# Power_Supply.net
KiCad netlist of a schematic drawn in Altium Designer
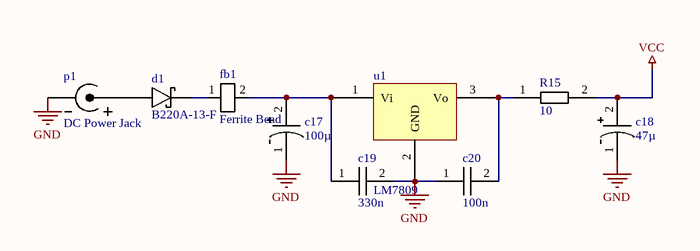
[diagram p0: Power Supply.SchDoc]

(export (version "E")
  (design (tool "Eeschema 10.0.6"))
  (components
    (comp (ref "c17")
      (value "100µ")
      (footprint "Elco-D")
      (description "Elco size D 6.3x5.4")
      (libsource (lib "Panasonic") (part "Elco D"))
    )
    (comp (ref "c18")
      (value "47µ")
      (footprint "Elco-D")
      (description "Elco size D 6.3x5.4")
      (libsource (lib "Panasonic") (part "Elco D"))
    )
    (comp (ref "c19")
      (value "330n")
      (footprint "0805")
      (description "0805 Capacitor Package")
      (libsource (lib "Generic R-C") (part "0805 Capacitor"))
    )
    (comp (ref "c20")
      (value "100n")
      (footprint "0805")
      (description "0805 Capacitor Package")
      (libsource (lib "Generic R-C") (part "0805 Capacitor"))
    )
    (comp (ref "d1")
      (value "B220A-13-F")
      (footprint "SMA")
      (description "Schottky Rectifier")
      (libsource (lib "Diodes_inc") (part "B220A-13-F"))
    )
    (comp (ref "fb1")
      (value "Ferrite Bead")
      (footprint "0805")
      (libsource (lib "TDK") (part "Ferrite Bead 0805 Package"))
    )
    (comp (ref "p1")
      (value "DC Power Jack")
      (footprint "Power Jack")
      (libsource (lib "Multicomp") (part "DC Power Jack"))
    )
    (comp (ref "R15")
      (value "10")
      (footprint "1206")
      (description "Resistor Package 1206")
      (libsource (lib "Generic R-C") (part "1206 Resistor"))
    )
    (comp (ref "u1")
      (value "LM7809")
      (footprint "TO-220AB-3")
      (description "Positive voltage regulator to 9V")
      (libsource (lib "Fairchild") (part "LM7809"))
    )
  )
  (nets
    (net (code "1") (name "GND") (class "Default")
      (node (ref "c17") (pin "1") (pintype "passive"))
      (node (ref "c18") (pin "1") (pintype "passive"))
      (node (ref "c19") (pin "2") (pintype "passive"))
      (node (ref "c20") (pin "1") (pintype "passive"))
      (node (ref "p1") (pin "2") (pinfunction "GND_2") (pintype "power_in"))
      (node (ref "u1") (pin "2") (pinfunction "GND_2") (pintype "power_in"))
    )
    (net (code "2") (name "Net-(d1-Anode)") (class "Default")
      (node (ref "d1") (pin "1") (pinfunction "Anode_1") (pintype "passive"))
      (node (ref "p1") (pin "1") (pinfunction "V+_1") (pintype "power_in"))
    )
    (net (code "3") (name "Net-(d1-Kathode)") (class "Default")
      (node (ref "d1") (pin "2") (pinfunction "Kathode_2") (pintype "passive"))
      (node (ref "fb1") (pin "1") (pintype "passive"))
    )
    (net (code "4") (name "Net-(u1-Vi)") (class "Default")
      (node (ref "c17") (pin "2") (pintype "passive"))
      (node (ref "c19") (pin "1") (pintype "passive"))
      (node (ref "fb1") (pin "2") (pintype "passive"))
      (node (ref "u1") (pin "1") (pinfunction "Vi_1") (pintype "power_in"))
    )
    (net (code "5") (name "Net-(u1-Vo)") (class "Default")
      (node (ref "R15") (pin "1") (pintype "passive"))
      (node (ref "c20") (pin "2") (pintype "passive"))
      (node (ref "u1") (pin "3") (pinfunction "Vo_3") (pintype "power_in"))
    )
    (net (code "6") (name "VCC") (class "Default")
      (node (ref "R15") (pin "2") (pintype "passive"))
      (node (ref "c18") (pin "2") (pintype "passive"))
    )
  )
)
